# Clock.net
KiCad netlist of a schematic drawn in Altium Designer
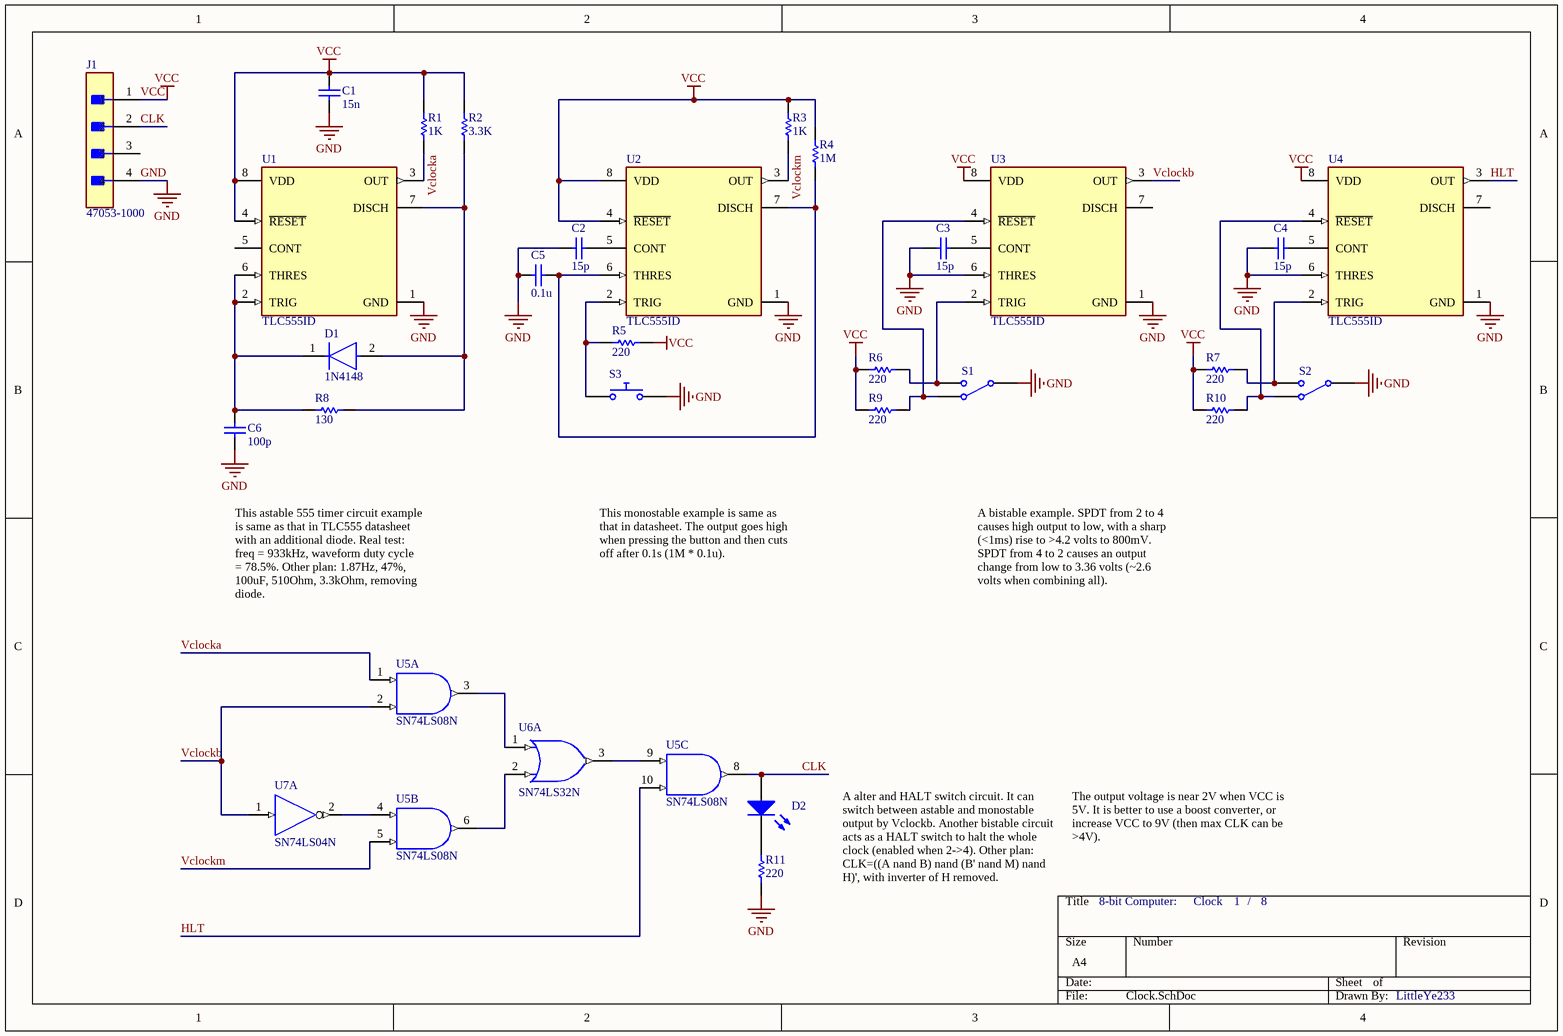
[diagram p0: Clock.SchDoc]

(export (version "E")
  (design (tool "Eeschema 10.0.6"))
  (components
    (comp (ref "C1")
      (value "15n")
      (description "Capacitor")
      (libsource (lib "Simulation Generic Components") (part "Capacitor"))
    )
    (comp (ref "C2")
      (value "15p")
      (description "Capacitor")
      (libsource (lib "Simulation Generic Components") (part "Capacitor"))
    )
    (comp (ref "C3")
      (value "15p")
      (description "Capacitor")
      (libsource (lib "Simulation Generic Components") (part "Capacitor"))
    )
    (comp (ref "C4")
      (value "15p")
      (description "Capacitor")
      (libsource (lib "Simulation Generic Components") (part "Capacitor"))
    )
    (comp (ref "C5")
      (value "0.1u")
      (description "Capacitor")
      (libsource (lib "Simulation Generic Components") (part "Capacitor"))
    )
    (comp (ref "C6")
      (value "100p")
      (description "Capacitor")
      (libsource (lib "Simulation Generic Components") (part "Capacitor"))
    )
    (comp (ref "D1")
      (value "1N4148")
      (footprint "FP-017AG-MFG")
      (description "DIODE GEN PURP 100V 200MA DO35")
      (fields (field (name "VOLTAGE") "100V"))
      (libsource (lib "1N4148") (part "CMP-07163-000046-1"))
    )
    (comp (ref "D2")
      (value "Light-Emitting Diode")
      (libsource (lib "Simulation Generic Components") (part "LED"))
    )
    (comp (ref "J1")
      (value "47053-1000")
      (footprint "FP-470531000-MFG")
      (description "CONN HEADER VERT 4POS 2.54MM")
      (libsource (lib "47053-1000") (part "CMP-04776-000290-2"))
    )
    (comp (ref "R1")
      (value "1K")
      (description "Resistor")
      (libsource (lib "Simulation Generic Components") (part "Resistor"))
    )
    (comp (ref "R2")
      (value "3.3K")
      (description "Resistor")
      (libsource (lib "Simulation Generic Components") (part "Resistor"))
    )
    (comp (ref "R3")
      (value "1K")
      (description "Resistor")
      (libsource (lib "Simulation Generic Components") (part "Resistor"))
    )
    (comp (ref "R4")
      (value "1M")
      (description "Resistor")
      (libsource (lib "Simulation Generic Components") (part "Resistor"))
    )
    (comp (ref "R5")
      (value "220")
      (description "Resistor")
      (libsource (lib "Simulation Generic Components") (part "Resistor"))
    )
    (comp (ref "R6")
      (value "220")
      (description "Resistor")
      (libsource (lib "Simulation Generic Components") (part "Resistor"))
    )
    (comp (ref "R7")
      (value "220")
      (description "Resistor")
      (libsource (lib "Simulation Generic Components") (part "Resistor"))
    )
    (comp (ref "R8")
      (value "130")
      (description "Resistor")
      (libsource (lib "Simulation Generic Components") (part "Resistor"))
    )
    (comp (ref "R9")
      (value "220")
      (description "Resistor")
      (libsource (lib "Simulation Generic Components") (part "Resistor"))
    )
    (comp (ref "R10")
      (value "220")
      (description "Resistor")
      (libsource (lib "Simulation Generic Components") (part "Resistor"))
    )
    (comp (ref "R11")
      (value "220")
      (description "Resistor")
      (libsource (lib "Simulation Generic Components") (part "Resistor"))
    )
    (comp (ref "S1")
      (value "Single-Pole, Double-Throw Switch")
      (libsource (lib "Simulation Generic Components") (part "SPDT SW"))
    )
    (comp (ref "S2")
      (value "Single-Pole, Double-Throw Switch")
      (libsource (lib "Simulation Generic Components") (part "SPDT SW"))
    )
    (comp (ref "S3")
      (value "Push Button Normally Opened")
      (libsource (lib "Simulation Generic Components") (part "Push Button NO"))
    )
    (comp (ref "U1")
      (value "TLC555ID")
      (footprint "FP-D0008A-IPC_B")
      (description "IC OSC SGL TIMER 2.1MHZ 8-SOIC")
      (fields
        (field (name "MANUFACTURER") "Texas Instruments")
        (field (name "OCTOPART") "https://octopart.com/tlc555id-texas+instruments-516571")
      )
      (libsource (lib "TLC555ID") (part "CMP-04858-000007-1"))
    )
    (comp (ref "U2")
      (value "TLC555ID")
      (footprint "FP-D0008A-IPC_B")
      (description "IC OSC SGL TIMER 2.1MHZ 8-SOIC")
      (fields
        (field (name "MANUFACTURER") "Texas Instruments")
        (field (name "OCTOPART") "https://octopart.com/tlc555id-texas+instruments-516571")
      )
      (libsource (lib "TLC555ID") (part "CMP-04858-000007-1"))
    )
    (comp (ref "U3")
      (value "TLC555ID")
      (footprint "FP-D0008A-IPC_B")
      (description "IC OSC SGL TIMER 2.1MHZ 8-SOIC")
      (fields
        (field (name "MANUFACTURER") "Texas Instruments")
        (field (name "OCTOPART") "https://octopart.com/tlc555id-texas+instruments-516571")
      )
      (libsource (lib "TLC555ID") (part "CMP-04858-000007-1"))
    )
    (comp (ref "U4")
      (value "TLC555ID")
      (footprint "FP-D0008A-IPC_B")
      (description "IC OSC SGL TIMER 2.1MHZ 8-SOIC")
      (fields
        (field (name "MANUFACTURER") "Texas Instruments")
        (field (name "OCTOPART") "https://octopart.com/tlc555id-texas+instruments-516571")
      )
      (libsource (lib "TLC555ID") (part "CMP-04858-000007-1"))
    )
    (comp (ref "U5")
      (value "SN74LS08N")
      (footprint "N0014A")
      (description "Quadruple 2-Input Positive-AND Gates, N0014A, TUBE")
      (fields
        (field (name "MANUFACTURER") "Texas Instruments")
        (field (name "GENERIC PART NUMBER") "SN74LS08")
      )
      (libsource (lib "SN74LS08N") (part "CMP-0777-00259-3"))
    )
    (comp (ref "U6")
      (value "SN74LS32N")
      (footprint "N0014A")
      (description "Quad 2-input positive-OR gates, N0014A, TUBE")
      (fields
        (field (name "GENERIC PART NUMBER") "SN74LS32")
        (field (name "MANUFACTURER") "Texas Instruments")
      )
      (libsource (lib "SN74LS32N") (part "CMP-1573-00145-3"))
    )
    (comp (ref "U7")
      (value "SN74LS04N")
      (footprint "N0014A")
      (description "Hex inverters, N0014A, TUBE")
      (fields
        (field (name "MANUFACTURER") "Texas Instruments")
        (field (name "GENERIC PART NUMBER") "SN74LS04")
      )
      (libsource (lib "SN74LS04N") (part "CMP-1615-00911-2"))
    )
  )
  (nets
    (net (code "1") (name "/CLK") (class "Default")
      (node (ref "D2") (pin "1") (pinfunction "A_1") (pintype "passive"))
      (node (ref "J1") (pin "2") (pinfunction "2_2") (pintype "passive"))
      (node (ref "U5") (pin "8") (pinfunction "3Y_8") (pintype "output"))
    )
    (net (code "2") (name "/HLT") (class "Default")
      (node (ref "U4") (pin "3") (pinfunction "OUT_3") (pintype "output"))
      (node (ref "U5") (pin "10") (pinfunction "3B_10") (pintype "input"))
    )
    (net (code "3") (name "/Vclocka") (class "Default")
      (node (ref "R1") (pin "1") (pinfunction "1_1") (pintype "passive"))
      (node (ref "U1") (pin "3") (pinfunction "OUT_3") (pintype "output"))
      (node (ref "U5") (pin "1") (pinfunction "1A_1") (pintype "input"))
    )
    (net (code "4") (name "/Vclockb") (class "Default")
      (node (ref "U3") (pin "3") (pinfunction "OUT_3") (pintype "output"))
      (node (ref "U5") (pin "2") (pinfunction "1B_2") (pintype "input"))
      (node (ref "U7") (pin "1") (pinfunction "1A_1") (pintype "input"))
    )
    (net (code "5") (name "/Vclockm") (class "Default")
      (node (ref "R3") (pin "1") (pinfunction "1_1") (pintype "passive"))
      (node (ref "U2") (pin "3") (pinfunction "OUT_3") (pintype "output"))
      (node (ref "U5") (pin "5") (pinfunction "2B_5") (pintype "input"))
    )
    (net (code "6") (name "GND") (class "Default")
      (node (ref "C1") (pin "1") (pinfunction "1_1") (pintype "passive"))
      (node (ref "C2") (pin "2") (pinfunction "2_2") (pintype "passive"))
      (node (ref "C3") (pin "2") (pinfunction "2_2") (pintype "passive"))
      (node (ref "C4") (pin "2") (pinfunction "2_2") (pintype "passive"))
      (node (ref "C5") (pin "2") (pinfunction "2_2") (pintype "passive"))
      (node (ref "C6") (pin "1") (pinfunction "1_1") (pintype "passive"))
      (node (ref "J1") (pin "4") (pinfunction "4_4") (pintype "passive"))
      (node (ref "R11") (pin "1") (pinfunction "1_1") (pintype "passive"))
      (node (ref "S1") (pin "1") (pinfunction "1_1") (pintype "passive"))
      (node (ref "S2") (pin "1") (pinfunction "1_1") (pintype "passive"))
      (node (ref "S3") (pin "2") (pinfunction "2_2") (pintype "passive"))
      (node (ref "U1") (pin "1") (pinfunction "GND_1") (pintype "power_in"))
      (node (ref "U2") (pin "1") (pinfunction "GND_1") (pintype "power_in"))
      (node (ref "U3") (pin "1") (pinfunction "GND_1") (pintype "power_in"))
      (node (ref "U3") (pin "6") (pinfunction "THRES_6") (pintype "input"))
      (node (ref "U4") (pin "1") (pinfunction "GND_1") (pintype "power_in"))
      (node (ref "U4") (pin "6") (pinfunction "THRES_6") (pintype "input"))
    )
    (net (code "7") (name "Net-(D1-A)") (class "Default")
      (node (ref "D1") (pin "2") (pinfunction "A_2") (pintype "passive"))
      (node (ref "R2") (pin "1") (pinfunction "1_1") (pintype "passive"))
      (node (ref "R8") (pin "2") (pinfunction "2_2") (pintype "passive"))
      (node (ref "U1") (pin "7") (pinfunction "DISCH_7") (pintype "open_collector"))
    )
    (net (code "8") (name "Net-(D1-C)") (class "Default")
      (node (ref "C6") (pin "2") (pinfunction "2_2") (pintype "passive"))
      (node (ref "D1") (pin "1") (pinfunction "C_1") (pintype "passive"))
      (node (ref "R8") (pin "1") (pinfunction "1_1") (pintype "passive"))
      (node (ref "U1") (pin "2") (pinfunction "TRIG_2") (pintype "input"))
      (node (ref "U1") (pin "6") (pinfunction "THRES_6") (pintype "input"))
    )
    (net (code "9") (name "Net-(D2-K)") (class "Default")
      (node (ref "D2") (pin "2") (pinfunction "K_2") (pintype "passive"))
      (node (ref "R11") (pin "2") (pinfunction "2_2") (pintype "passive"))
    )
    (net (code "10") (name "Net-(U2-CONT)") (class "Default")
      (node (ref "C2") (pin "1") (pinfunction "1_1") (pintype "passive"))
      (node (ref "U2") (pin "5") (pinfunction "CONT_5") (pintype "passive"))
    )
    (net (code "11") (name "Net-(U2-DISCH)") (class "Default")
      (node (ref "C5") (pin "1") (pinfunction "1_1") (pintype "passive"))
      (node (ref "R4") (pin "1") (pinfunction "1_1") (pintype "passive"))
      (node (ref "U2") (pin "6") (pinfunction "THRES_6") (pintype "input"))
      (node (ref "U2") (pin "7") (pinfunction "DISCH_7") (pintype "open_collector"))
    )
    (net (code "12") (name "Net-(U2-TRIG)") (class "Default")
      (node (ref "R5") (pin "2") (pinfunction "2_2") (pintype "passive"))
      (node (ref "S3") (pin "1") (pinfunction "1_1") (pintype "passive"))
      (node (ref "U2") (pin "2") (pinfunction "TRIG_2") (pintype "input"))
    )
    (net (code "13") (name "Net-(U3-CONT)") (class "Default")
      (node (ref "C3") (pin "1") (pinfunction "1_1") (pintype "passive"))
      (node (ref "U3") (pin "5") (pinfunction "CONT_5") (pintype "passive"))
    )
    (net (code "14") (name "Net-(U3-TRIG)") (class "Default")
      (node (ref "R6") (pin "2") (pinfunction "2_2") (pintype "passive"))
      (node (ref "S1") (pin "2") (pinfunction "2_2") (pintype "passive"))
      (node (ref "U3") (pin "2") (pinfunction "TRIG_2") (pintype "input"))
    )
    (net (code "15") (name "Net-(U3-~{RESET})") (class "Default")
      (node (ref "R9") (pin "1") (pinfunction "1_1") (pintype "passive"))
      (node (ref "S1") (pin "3") (pinfunction "3_3") (pintype "passive"))
      (node (ref "U3") (pin "4") (pinfunction "~{RESET}_4") (pintype "input"))
    )
    (net (code "16") (name "Net-(U4-CONT)") (class "Default")
      (node (ref "C4") (pin "1") (pinfunction "1_1") (pintype "passive"))
      (node (ref "U4") (pin "5") (pinfunction "CONT_5") (pintype "passive"))
    )
    (net (code "17") (name "Net-(U4-TRIG)") (class "Default")
      (node (ref "R7") (pin "2") (pinfunction "2_2") (pintype "passive"))
      (node (ref "S2") (pin "2") (pinfunction "2_2") (pintype "passive"))
      (node (ref "U4") (pin "2") (pinfunction "TRIG_2") (pintype "input"))
    )
    (net (code "18") (name "Net-(U4-~{RESET})") (class "Default")
      (node (ref "R10") (pin "1") (pinfunction "1_1") (pintype "passive"))
      (node (ref "S2") (pin "3") (pinfunction "3_3") (pintype "passive"))
      (node (ref "U4") (pin "4") (pinfunction "~{RESET}_4") (pintype "input"))
    )
    (net (code "19") (name "Net-(U5A-1Y)") (class "Default")
      (node (ref "U5") (pin "3") (pinfunction "1Y_3") (pintype "output"))
      (node (ref "U6") (pin "1") (pinfunction "1A_1") (pintype "input"))
    )
    (net (code "20") (name "Net-(U5B-2A)") (class "Default")
      (node (ref "U5") (pin "4") (pinfunction "2A_4") (pintype "input"))
      (node (ref "U7") (pin "2") (pinfunction "~{1Y}_2") (pintype "output"))
    )
    (net (code "21") (name "Net-(U5B-2Y)") (class "Default")
      (node (ref "U5") (pin "6") (pinfunction "2Y_6") (pintype "output"))
      (node (ref "U6") (pin "2") (pinfunction "1B_2") (pintype "input"))
    )
    (net (code "22") (name "Net-(U5C-3A)") (class "Default")
      (node (ref "U5") (pin "9") (pinfunction "3A_9") (pintype "input"))
      (node (ref "U6") (pin "3") (pinfunction "1Y_3") (pintype "output"))
    )
    (net (code "23") (name "VCC") (class "Default")
      (node (ref "C1") (pin "2") (pinfunction "2_2") (pintype "passive"))
      (node (ref "J1") (pin "1") (pinfunction "1_1") (pintype "passive"))
      (node (ref "R1") (pin "2") (pinfunction "2_2") (pintype "passive"))
      (node (ref "R10") (pin "2") (pinfunction "2_2") (pintype "passive"))
      (node (ref "R2") (pin "2") (pinfunction "2_2") (pintype "passive"))
      (node (ref "R3") (pin "2") (pinfunction "2_2") (pintype "passive"))
      (node (ref "R4") (pin "2") (pinfunction "2_2") (pintype "passive"))
      (node (ref "R5") (pin "1") (pinfunction "1_1") (pintype "passive"))
      (node (ref "R6") (pin "1") (pinfunction "1_1") (pintype "passive"))
      (node (ref "R7") (pin "1") (pinfunction "1_1") (pintype "passive"))
      (node (ref "R9") (pin "2") (pinfunction "2_2") (pintype "passive"))
      (node (ref "U1") (pin "4") (pinfunction "~{RESET}_4") (pintype "input"))
      (node (ref "U1") (pin "8") (pinfunction "VDD_8") (pintype "power_in"))
      (node (ref "U2") (pin "4") (pinfunction "~{RESET}_4") (pintype "input"))
      (node (ref "U2") (pin "8") (pinfunction "VDD_8") (pintype "power_in"))
      (node (ref "U3") (pin "8") (pinfunction "VDD_8") (pintype "power_in"))
      (node (ref "U4") (pin "8") (pinfunction "VDD_8") (pintype "power_in"))
    )
    (net (code "24") (name "unconnected-(J1-Pad3)") (class "Default")
      (node (ref "J1") (pin "3") (pinfunction "3_3") (pintype "passive"))
    )
    (net (code "25") (name "unconnected-(U1-CONT-Pad5)") (class "Default")
      (node (ref "U1") (pin "5") (pinfunction "CONT_5") (pintype "passive"))
    )
    (net (code "26") (name "unconnected-(U3-DISCH-Pad7)") (class "Default")
      (node (ref "U3") (pin "7") (pinfunction "DISCH_7") (pintype "open_collector"))
    )
    (net (code "27") (name "unconnected-(U4-DISCH-Pad7)") (class "Default")
      (node (ref "U4") (pin "7") (pinfunction "DISCH_7") (pintype "open_collector"))
    )
  )
)
